# LM2596_Schematic.net
KiCad netlist of a schematic drawn in Altium Designer
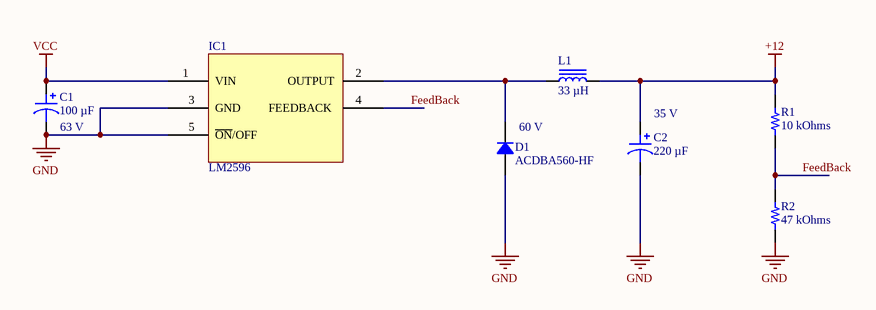
[diagram p0: LM2596_Schematic.SchDoc]

(export (version "E")
  (design (tool "Eeschema 10.0.6"))
  (components
    (comp (ref "C1")
      (value "100 µF")
      (footprint "CAP AL TH D8 L3.5 H12.5")
      (description "CAP ALUM 100UF 20% 63V RADIAL")
      (fields
        (field (name "PART NUMBER") "ECA-1JM101")
        (field (name "MANUFACTURER") "Panasonic Electronic Components")
        (field (name "VOLTAGE - RATED") "63 V")
      )
      (libsource (lib "Celestial Altium Library - altium_library") (part "Polarised Capacitor"))
    )
    (comp (ref "C2")
      (value "220 µF")
      (footprint "CAP AL TH D8 L3.5 H12.5")
      (description "CAP ALUM 220UF 20% 35V RADIAL")
      (fields
        (field (name "PART NUMBER") "ECA-1VM221")
        (field (name "MANUFACTURER") "Panasonic Electronic Components")
        (field (name "VOLTAGE - RATED") "35 V")
      )
      (libsource (lib "Celestial Altium Library - altium_library") (part "Polarised Capacitor"))
    )
    (comp (ref "D1")
      (value "ACDBA560-HF")
      (footprint "DO214AC SMA")
      (description "DIODE SCHOTTKY 60V 5A DO214AC")
      (fields
        (field (name "MANUFACTURER") "Comchip Technology")
        (field (name "VOLTAGE - DC REVERSE (VR) (MAX)") "60 V")
      )
      (libsource (lib "Celestial Altium Library - altium_library") (part "Diode"))
    )
    (comp (ref "IC1")
      (value "LM2596")
      (footprint "LM2596_DC-DC:D2PAK")
      (libsource (lib "LM2596") (part "LM2596"))
    )
    (comp (ref "L1")
      (value "33 µH")
      (footprint "BOURNS SRR1280")
      (description "FIXED IND 33UH 3.5A 57 MOHM SMD")
      (fields (field (name "PART NUMBER") "SRR1280-330M") (field (name "MANUFACTURER") "Bourns Inc."))
      (libsource (lib "Celestial Altium Library - altium_library") (part "Inductor"))
    )
    (comp (ref "R1")
      (value "10 kOhms")
      (footprint "RES 0805_2012")
      (description "RES 10K OHM 0.1% 1/10W 0805")
      (fields
        (field (name "PART NUMBER") "RNCS0805BKE10K0")
        (field (name "MANUFACTURER") "Stackpole Electronics Inc")
      )
      (libsource (lib "Celestial Altium Library - altium_library") (part "Resistor"))
    )
    (comp (ref "R2")
      (value "47 kOhms")
      (footprint "RES 0805_2012")
      (description "RES 47K OHM 1% 1/3W 0805")
      (fields
        (field (name "PART NUMBER") "CRGP0805F47K")
        (field (name "MANUFACTURER") "TE Connectivity Passive Product")
      )
      (libsource (lib "Celestial Altium Library - altium_library") (part "Resistor"))
    )
  )
  (nets
    (net (code "1") (name "+12") (class "Default")
      (node (ref "C2") (pin "1") (pinfunction "1_1") (pintype "passive"))
      (node (ref "L1") (pin "2") (pinfunction "2_2") (pintype "passive"))
      (node (ref "R1") (pin "2") (pinfunction "2_2") (pintype "passive"))
    )
    (net (code "2") (name "/FeedBack") (class "Default")
      (node (ref "IC1") (pin "4") (pinfunction "FEEDBACK_4") (pintype "passive"))
      (node (ref "R1") (pin "1") (pinfunction "1_1") (pintype "passive"))
      (node (ref "R2") (pin "2") (pinfunction "2_2") (pintype "passive"))
    )
    (net (code "3") (name "GND") (class "Default")
      (node (ref "C1") (pin "2") (pinfunction "2_2") (pintype "passive"))
      (node (ref "C2") (pin "2") (pinfunction "2_2") (pintype "passive"))
      (node (ref "D1") (pin "1") (pinfunction "1_1") (pintype "passive"))
      (node (ref "IC1") (pin "3") (pinfunction "GND_3") (pintype "passive"))
      (node (ref "IC1") (pin "5") (pinfunction "~{ON}/OFF_5") (pintype "passive"))
      (node (ref "R2") (pin "1") (pinfunction "1_1") (pintype "passive"))
    )
    (net (code "4") (name "Net-(IC1-OUTPUT)") (class "Default")
      (node (ref "D1") (pin "2") (pinfunction "2_2") (pintype "passive"))
      (node (ref "IC1") (pin "2") (pinfunction "OUTPUT_2") (pintype "passive"))
      (node (ref "L1") (pin "1") (pinfunction "1_1") (pintype "passive"))
    )
    (net (code "5") (name "VCC") (class "Default")
      (node (ref "C1") (pin "1") (pinfunction "1_1") (pintype "passive"))
      (node (ref "IC1") (pin "1") (pinfunction "VIN_1") (pintype "passive"))
    )
  )
)
